# leaf_type_02_rev_01.net
KiCad netlist of a schematic drawn in EAGLE
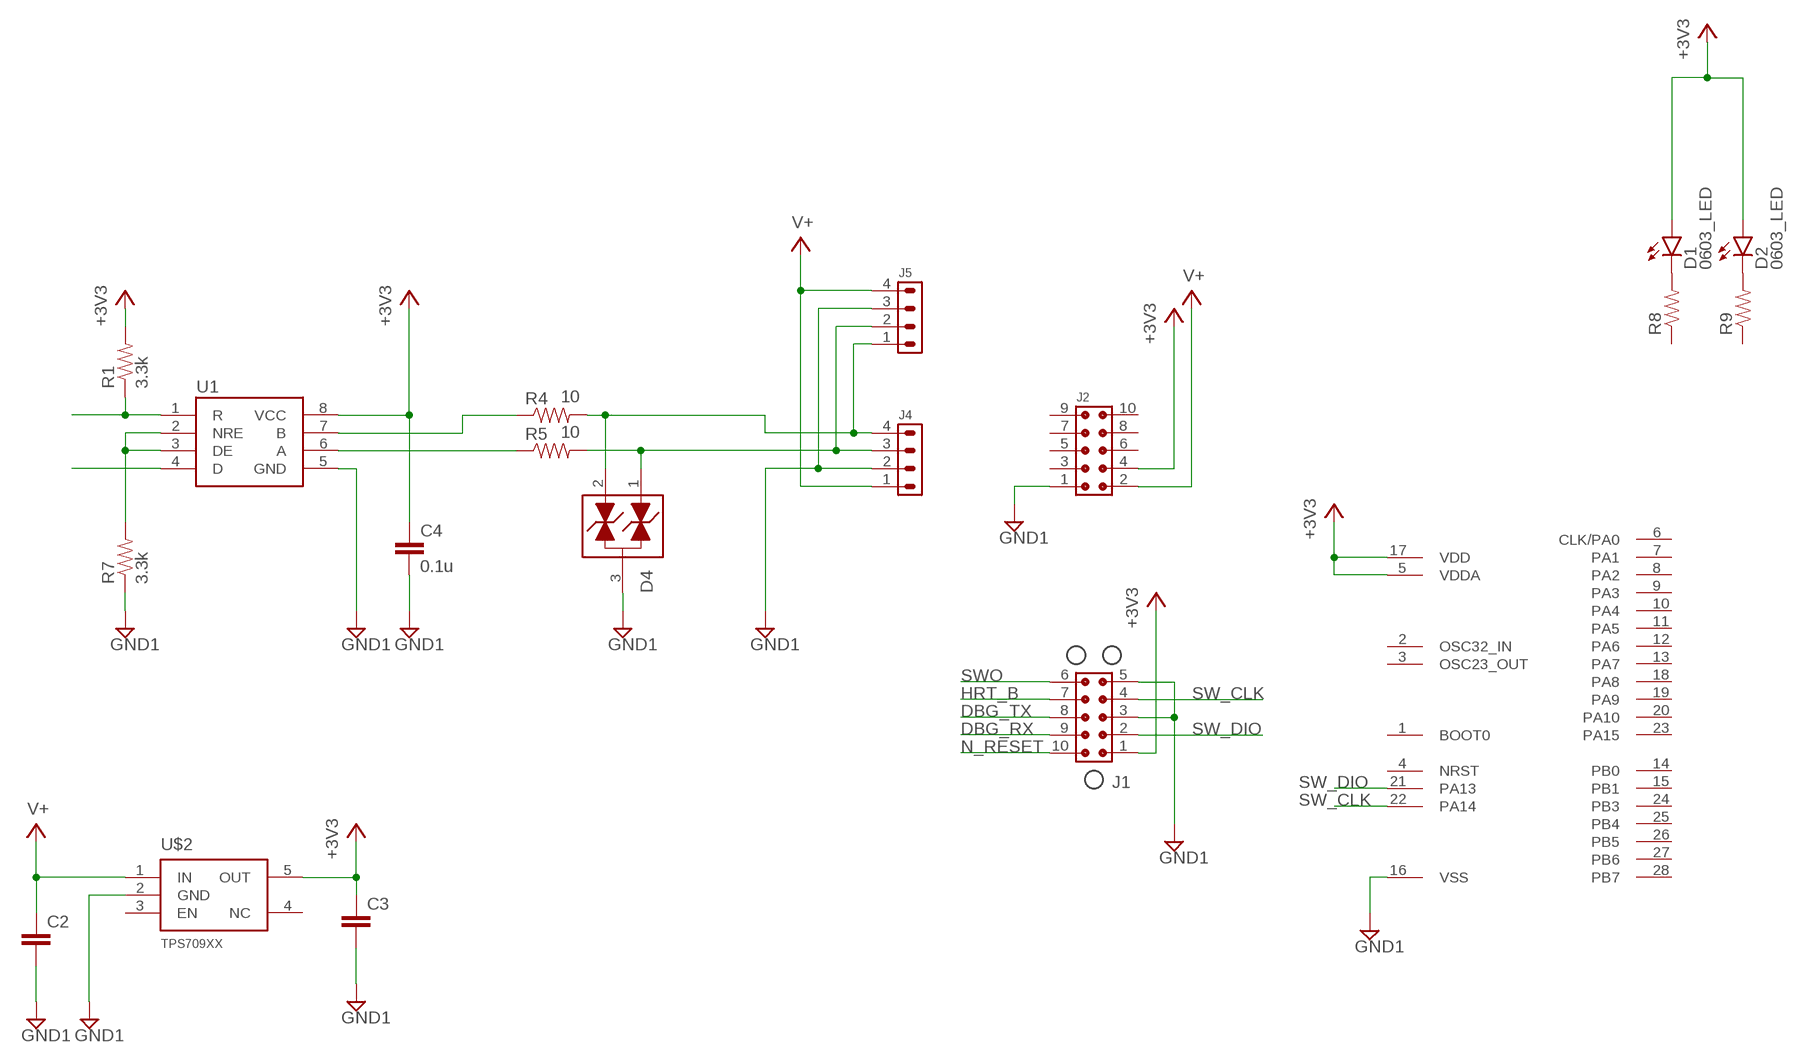
[diagram p0: schematic, sheet 1]

(export (version "E")
  (design (tool "Eeschema 10.0.6"))
  (components
    (comp (ref "C2")
      (value "0603_CAP")
      (footprint "eagle-import:0603")
      (libsource (lib "eagle-import") (part "0603_CAP"))
    )
    (comp (ref "C3")
      (value "0603_CAP")
      (footprint "eagle-import:0603")
      (libsource (lib "eagle-import") (part "0603_CAP"))
    )
    (comp (ref "C4")
      (value "0.1u")
      (footprint "eagle-import:0603")
      (libsource (lib "eagle-import") (part "0603_CAP"))
    )
    (comp (ref "D1")
      (value "0603_LED")
      (footprint "eagle-import:0603_LED")
      (libsource (lib "eagle-import") (part "0603_LED"))
    )
    (comp (ref "D2")
      (value "0603_LED")
      (footprint "eagle-import:0603_LED")
      (libsource (lib "eagle-import") (part "0603_LED"))
    )
    (comp (ref "D4")
      (value "TVS_SOT-23")
      (footprint "eagle-import:SOT-23_ONSEMI")
      (libsource (lib "eagle-import") (part "TVS_SOT-23"))
    )
    (comp (ref "J1")
      (value "TC_2050_IDC_NL_TOP")
      (footprint "eagle-import:TC_2050_IDC_NL_TOP")
      (libsource (lib "eagle-import") (part "TC_2050_IDC_NL_TOP"))
    )
    (comp (ref "J2")
      (value "CONN_5X2_0P05_IN_SMT")
      (footprint "eagle-import:CONN_5X2_0P050_IN_SMT")
      (libsource (lib "eagle-import") (part "CONN_5X2_0P05_IN_SMT"))
    )
    (comp (ref "J4")
      (value "CONN_4X1_JST_PA")
      (footprint "eagle-import:CONN_4X1_JST_PA")
      (libsource (lib "eagle-import") (part "CONN_4X1_JST_PA"))
    )
    (comp (ref "J5")
      (value "CONN_4X1_JST_PA")
      (footprint "eagle-import:CONN_4X1_JST_PA")
      (libsource (lib "eagle-import") (part "CONN_4X1_JST_PA"))
    )
    (comp (ref "R1")
      (value "3.3k")
      (footprint "eagle-import:0402")
      (libsource (lib "eagle-import") (part "0402_RES"))
    )
    (comp (ref "R4")
      (value "10")
      (footprint "eagle-import:0603")
      (libsource (lib "eagle-import") (part "0603_RES"))
    )
    (comp (ref "R5")
      (value "10")
      (footprint "eagle-import:0603")
      (libsource (lib "eagle-import") (part "0603_RES"))
    )
    (comp (ref "R7")
      (value "3.3k")
      (footprint "eagle-import:0603")
      (libsource (lib "eagle-import") (part "0603_RES"))
    )
    (comp (ref "R8")
      (value "0603_RES")
      (footprint "eagle-import:0603")
      (libsource (lib "eagle-import") (part "0603_RES"))
    )
    (comp (ref "R9")
      (value "0603_RES")
      (footprint "eagle-import:0603")
      (libsource (lib "eagle-import") (part "0603_RES"))
    )
    (comp (ref "U$2")
      (value "TPS709XX")
      (footprint "eagle-import:SOT23-5")
      (libsource (lib "eagle-import") (part "TPS709XX"))
    )
    (comp (ref "U1")
      (value "RS485_XCVR_SN65HVD178X")
      (footprint "eagle-import:SOIC_08_TI")
      (libsource (lib "eagle-import") (part "RS485_XCVR_SN65HVD178X"))
    )
    (comp (ref "U2")
      (value "STM32L031G6U6")
      (footprint "eagle-import:STM32_QFN_28_4X4")
      (libsource (lib "eagle-import") (part "STM32L031G6U6"))
    )
  )
  (nets
    (net (code "1") (name "+3V3") (class "Default")
      (node (ref "C3") (pin "P$1") (pinfunction "1_P$1") (pintype "passive"))
      (node (ref "C4") (pin "P$1") (pinfunction "1_P$1") (pintype "passive"))
      (node (ref "D1") (pin "P$1") (pinfunction "A_P$1") (pintype "passive"))
      (node (ref "D2") (pin "P$1") (pinfunction "A_P$1") (pintype "passive"))
      (node (ref "J1") (pin "1") (pinfunction "1_1") (pintype "bidirectional"))
      (node (ref "J2") (pin "4") (pinfunction "4_4") (pintype "bidirectional"))
      (node (ref "R1") (pin "P$2") (pinfunction "2_P$2") (pintype "passive"))
      (node (ref "U$2") (pin "5") (pinfunction "OUT_5") (pintype "bidirectional"))
      (node (ref "U1") (pin "8") (pinfunction "VCC_8") (pintype "bidirectional"))
      (node (ref "U2") (pin "17") (pinfunction "VDD_17") (pintype "bidirectional"))
      (node (ref "U2") (pin "5") (pinfunction "VDDA_5") (pintype "bidirectional"))
    )
    (net (code "2") (name "/DBG_RX") (class "Default")
      (node (ref "J1") (pin "9") (pinfunction "9_9") (pintype "bidirectional"))
    )
    (net (code "3") (name "/DBG_TX") (class "Default")
      (node (ref "J1") (pin "8") (pinfunction "8_8") (pintype "bidirectional"))
    )
    (net (code "4") (name "/HRT_B") (class "Default")
      (node (ref "J1") (pin "7") (pinfunction "7_7") (pintype "bidirectional"))
    )
    (net (code "5") (name "/N_RESET") (class "Default")
      (node (ref "J1") (pin "10") (pinfunction "10_10") (pintype "bidirectional"))
    )
    (net (code "6") (name "/SWO") (class "Default")
      (node (ref "J1") (pin "6") (pinfunction "6_6") (pintype "bidirectional"))
    )
    (net (code "7") (name "/SW_CLK") (class "Default")
      (node (ref "J1") (pin "4") (pinfunction "4_4") (pintype "bidirectional"))
      (node (ref "U2") (pin "22") (pinfunction "PA14_22") (pintype "bidirectional"))
    )
    (net (code "8") (name "/SW_DIO") (class "Default")
      (node (ref "J1") (pin "2") (pinfunction "2_2") (pintype "bidirectional"))
      (node (ref "U2") (pin "21") (pinfunction "PA13_21") (pintype "bidirectional"))
    )
    (net (code "9") (name "GND1") (class "Default")
      (node (ref "C2") (pin "P$2") (pinfunction "2_P$2") (pintype "passive"))
      (node (ref "C3") (pin "P$2") (pinfunction "2_P$2") (pintype "passive"))
      (node (ref "C4") (pin "P$2") (pinfunction "2_P$2") (pintype "passive"))
      (node (ref "D4") (pin "3") (pinfunction "3_3") (pintype "bidirectional"))
      (node (ref "J1") (pin "3") (pinfunction "3_3") (pintype "bidirectional"))
      (node (ref "J1") (pin "5") (pinfunction "5_5") (pintype "bidirectional"))
      (node (ref "J2") (pin "1") (pinfunction "1_1") (pintype "bidirectional"))
      (node (ref "J4") (pin "2") (pinfunction "2_2") (pintype "bidirectional"))
      (node (ref "J5") (pin "3") (pinfunction "3_3") (pintype "bidirectional"))
      (node (ref "R7") (pin "P$1") (pinfunction "1_P$1") (pintype "passive"))
      (node (ref "U$2") (pin "2") (pinfunction "GND_2") (pintype "bidirectional"))
      (node (ref "U1") (pin "5") (pinfunction "GND_5") (pintype "bidirectional"))
      (node (ref "U2") (pin "16") (pinfunction "VSS_16") (pintype "bidirectional"))
    )
    (net (code "10") (name "Net-(D1-C)") (class "Default")
      (node (ref "D1") (pin "P$2") (pinfunction "C_P$2") (pintype "passive"))
      (node (ref "R8") (pin "P$2") (pinfunction "2_P$2") (pintype "passive"))
    )
    (net (code "11") (name "Net-(D2-C)") (class "Default")
      (node (ref "D2") (pin "P$2") (pinfunction "C_P$2") (pintype "passive"))
      (node (ref "R9") (pin "P$2") (pinfunction "2_P$2") (pintype "passive"))
    )
    (net (code "12") (name "Net-(R1-1)") (class "Default")
      (node (ref "R1") (pin "P$1") (pinfunction "1_P$1") (pintype "passive"))
      (node (ref "U1") (pin "1") (pinfunction "R_1") (pintype "bidirectional"))
    )
    (net (code "13") (name "Net-(R4-1)") (class "Default")
      (node (ref "R4") (pin "P$1") (pinfunction "1_P$1") (pintype "passive"))
      (node (ref "U1") (pin "7") (pinfunction "B_7") (pintype "bidirectional"))
    )
    (net (code "14") (name "Net-(R4-2)") (class "Default")
      (node (ref "D4") (pin "2") (pinfunction "2_2") (pintype "bidirectional"))
      (node (ref "J4") (pin "4") (pinfunction "4_4") (pintype "bidirectional"))
      (node (ref "J5") (pin "1") (pinfunction "1_1") (pintype "bidirectional"))
      (node (ref "R4") (pin "P$2") (pinfunction "2_P$2") (pintype "passive"))
    )
    (net (code "15") (name "Net-(R5-1)") (class "Default")
      (node (ref "R5") (pin "P$1") (pinfunction "1_P$1") (pintype "passive"))
      (node (ref "U1") (pin "6") (pinfunction "A_6") (pintype "bidirectional"))
    )
    (net (code "16") (name "Net-(R5-2)") (class "Default")
      (node (ref "D4") (pin "1") (pinfunction "1_1") (pintype "bidirectional"))
      (node (ref "J4") (pin "3") (pinfunction "3_3") (pintype "bidirectional"))
      (node (ref "J5") (pin "2") (pinfunction "2_2") (pintype "bidirectional"))
      (node (ref "R5") (pin "P$2") (pinfunction "2_P$2") (pintype "passive"))
    )
    (net (code "17") (name "Net-(R7-2)") (class "Default")
      (node (ref "R7") (pin "P$2") (pinfunction "2_P$2") (pintype "passive"))
      (node (ref "U1") (pin "2") (pinfunction "NRE_2") (pintype "bidirectional"))
      (node (ref "U1") (pin "3") (pinfunction "DE_3") (pintype "bidirectional"))
    )
    (net (code "18") (name "V+") (class "Default")
      (node (ref "C2") (pin "P$1") (pinfunction "1_P$1") (pintype "passive"))
      (node (ref "J2") (pin "2") (pinfunction "2_2") (pintype "bidirectional"))
      (node (ref "J4") (pin "1") (pinfunction "1_1") (pintype "bidirectional"))
      (node (ref "J5") (pin "4") (pinfunction "4_4") (pintype "bidirectional"))
      (node (ref "U$2") (pin "1") (pinfunction "IN_1") (pintype "bidirectional"))
    )
    (net (code "19") (name "unconnected-(J2-Pad3)") (class "Default")
      (node (ref "J2") (pin "3") (pinfunction "3_3") (pintype "bidirectional"))
    )
    (net (code "20") (name "unconnected-(J2-Pad5)") (class "Default")
      (node (ref "J2") (pin "5") (pinfunction "5_5") (pintype "bidirectional"))
    )
    (net (code "21") (name "unconnected-(J2-Pad6)") (class "Default")
      (node (ref "J2") (pin "6") (pinfunction "6_6") (pintype "bidirectional"))
    )
    (net (code "22") (name "unconnected-(J2-Pad7)") (class "Default")
      (node (ref "J2") (pin "7") (pinfunction "7_7") (pintype "bidirectional"))
    )
    (net (code "23") (name "unconnected-(J2-Pad8)") (class "Default")
      (node (ref "J2") (pin "8") (pinfunction "8_8") (pintype "bidirectional"))
    )
    (net (code "24") (name "unconnected-(J2-Pad9)") (class "Default")
      (node (ref "J2") (pin "9") (pinfunction "9_9") (pintype "bidirectional"))
    )
    (net (code "25") (name "unconnected-(J2-Pad10)") (class "Default")
      (node (ref "J2") (pin "10") (pinfunction "10_10") (pintype "bidirectional"))
    )
    (net (code "26") (name "unconnected-(R8-1-PadP$1)") (class "Default")
      (node (ref "R8") (pin "P$1") (pinfunction "1_P$1") (pintype "passive"))
    )
    (net (code "27") (name "unconnected-(R9-1-PadP$1)") (class "Default")
      (node (ref "R9") (pin "P$1") (pinfunction "1_P$1") (pintype "passive"))
    )
    (net (code "28") (name "unconnected-(U$2-EN-Pad3)") (class "Default")
      (node (ref "U$2") (pin "3") (pinfunction "EN_3") (pintype "bidirectional"))
    )
    (net (code "29") (name "unconnected-(U$2-NC-Pad4)") (class "Default")
      (node (ref "U$2") (pin "4") (pinfunction "NC_4") (pintype "bidirectional"))
    )
    (net (code "30") (name "unconnected-(U1-D-Pad4)") (class "Default")
      (node (ref "U1") (pin "4") (pinfunction "D_4") (pintype "bidirectional"))
    )
    (net (code "31") (name "unconnected-(U2-BOOT0-Pad1)") (class "Default")
      (node (ref "U2") (pin "1") (pinfunction "BOOT0_1") (pintype "bidirectional"))
    )
    (net (code "32") (name "unconnected-(U2-CLK{slash}PA0-Pad6)") (class "Default")
      (node (ref "U2") (pin "6") (pinfunction "CLK/PA0_6") (pintype "bidirectional"))
    )
    (net (code "33") (name "unconnected-(U2-NRST-Pad4)") (class "Default")
      (node (ref "U2") (pin "4") (pinfunction "NRST_4") (pintype "bidirectional"))
    )
    (net (code "34") (name "unconnected-(U2-OSC23_OUT-Pad3)") (class "Default")
      (node (ref "U2") (pin "3") (pinfunction "OSC23_OUT_3") (pintype "bidirectional"))
    )
    (net (code "35") (name "unconnected-(U2-OSC32_IN-Pad2)") (class "Default")
      (node (ref "U2") (pin "2") (pinfunction "OSC32_IN_2") (pintype "bidirectional"))
    )
    (net (code "36") (name "unconnected-(U2-PA1-Pad7)") (class "Default")
      (node (ref "U2") (pin "7") (pinfunction "PA1_7") (pintype "bidirectional"))
    )
    (net (code "37") (name "unconnected-(U2-PA2-Pad8)") (class "Default")
      (node (ref "U2") (pin "8") (pinfunction "PA2_8") (pintype "bidirectional"))
    )
    (net (code "38") (name "unconnected-(U2-PA3-Pad9)") (class "Default")
      (node (ref "U2") (pin "9") (pinfunction "PA3_9") (pintype "bidirectional"))
    )
    (net (code "39") (name "unconnected-(U2-PA4-Pad10)") (class "Default")
      (node (ref "U2") (pin "10") (pinfunction "PA4_10") (pintype "bidirectional"))
    )
    (net (code "40") (name "unconnected-(U2-PA5-Pad11)") (class "Default")
      (node (ref "U2") (pin "11") (pinfunction "PA5_11") (pintype "bidirectional"))
    )
    (net (code "41") (name "unconnected-(U2-PA6-Pad12)") (class "Default")
      (node (ref "U2") (pin "12") (pinfunction "PA6_12") (pintype "bidirectional"))
    )
    (net (code "42") (name "unconnected-(U2-PA7-Pad13)") (class "Default")
      (node (ref "U2") (pin "13") (pinfunction "PA7_13") (pintype "bidirectional"))
    )
    (net (code "43") (name "unconnected-(U2-PA8-Pad18)") (class "Default")
      (node (ref "U2") (pin "18") (pinfunction "PA8_18") (pintype "bidirectional"))
    )
    (net (code "44") (name "unconnected-(U2-PA9-Pad19)") (class "Default")
      (node (ref "U2") (pin "19") (pinfunction "PA9_19") (pintype "bidirectional"))
    )
    (net (code "45") (name "unconnected-(U2-PA10-Pad20)") (class "Default")
      (node (ref "U2") (pin "20") (pinfunction "PA10_20") (pintype "bidirectional"))
    )
    (net (code "46") (name "unconnected-(U2-PA15-Pad23)") (class "Default")
      (node (ref "U2") (pin "23") (pinfunction "PA15_23") (pintype "bidirectional"))
    )
    (net (code "47") (name "unconnected-(U2-PB0-Pad14)") (class "Default")
      (node (ref "U2") (pin "14") (pinfunction "PB0_14") (pintype "bidirectional"))
    )
    (net (code "48") (name "unconnected-(U2-PB1-Pad15)") (class "Default")
      (node (ref "U2") (pin "15") (pinfunction "PB1_15") (pintype "bidirectional"))
    )
    (net (code "49") (name "unconnected-(U2-PB3-Pad24)") (class "Default")
      (node (ref "U2") (pin "24") (pinfunction "PB3_24") (pintype "bidirectional"))
    )
    (net (code "50") (name "unconnected-(U2-PB4-Pad25)") (class "Default")
      (node (ref "U2") (pin "25") (pinfunction "PB4_25") (pintype "bidirectional"))
    )
    (net (code "51") (name "unconnected-(U2-PB5-Pad26)") (class "Default")
      (node (ref "U2") (pin "26") (pinfunction "PB5_26") (pintype "bidirectional"))
    )
    (net (code "52") (name "unconnected-(U2-PB6-Pad27)") (class "Default")
      (node (ref "U2") (pin "27") (pinfunction "PB6_27") (pintype "bidirectional"))
    )
    (net (code "53") (name "unconnected-(U2-PB7-Pad28)") (class "Default")
      (node (ref "U2") (pin "28") (pinfunction "PB7_28") (pintype "bidirectional"))
    )
  )
)
